# RF19_Sensor_CAN_Module_MCU.net
KiCad netlist of a schematic drawn in Altium Designer
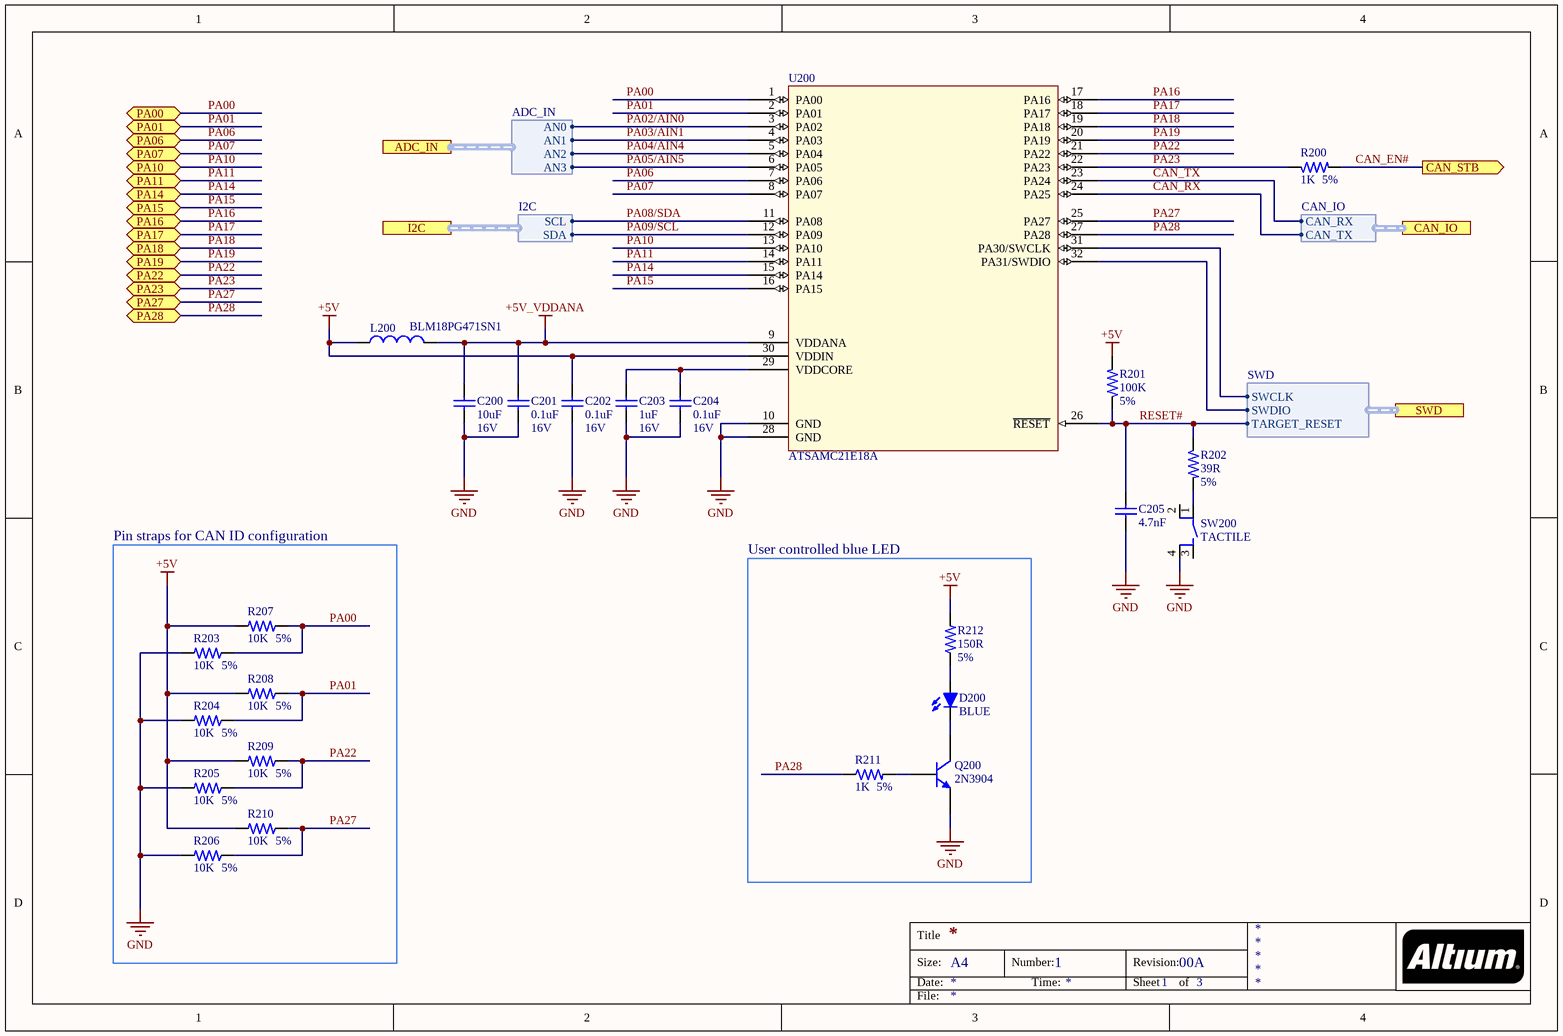
[diagram p0: RF19_Sensor_CAN_Module_MCU.SchDoc]

(export (version "E")
  (design (tool "Eeschema 10.0.6"))
  (components
    (comp (ref "C200")
      (value "10uF")
      (footprint "C0603")
      (description "Ceramic cap, 10uF +/-10% 16V X5R 0603")
      (fields (field (name "VOLTAGE") "16V") (field (name "Comment") "CERAMIC CAP"))
      (libsource (lib "Custom") (part "C010U10P16VX5R0603"))
    )
    (comp (ref "C201")
      (value "0.1uF")
      (footprint "C0402")
      (description "Ceramic cap, 0.1uF +/-10% 16V X5R 0402")
      (fields (field (name "VOLTAGE") "16V") (field (name "Comment") "CERAMIC CAP"))
      (libsource (lib "Custom") (part "C00U110P16VX5R0402"))
    )
    (comp (ref "C202")
      (value "0.1uF")
      (footprint "C0402")
      (description "Ceramic cap, 0.1uF +/-10% 16V X5R 0402")
      (fields (field (name "VOLTAGE") "16V") (field (name "Comment") "CERAMIC CAP"))
      (libsource (lib "Custom") (part "C00U110P16VX5R0402"))
    )
    (comp (ref "C203")
      (value "1uF")
      (footprint "C0402")
      (description "Ceramic cap, 1uF +/-10% 16V X5R 0402")
      (fields (field (name "VOLTAGE") "16V") (field (name "Comment") "CERAMIC CAP"))
      (libsource (lib "Custom") (part "C001U10P16VX5R0402"))
    )
    (comp (ref "C204")
      (value "0.1uF")
      (footprint "C0402")
      (description "Ceramic cap, 0.1uF +/-10% 16V X5R 0402")
      (fields (field (name "VOLTAGE") "16V") (field (name "Comment") "CERAMIC CAP"))
      (libsource (lib "Custom") (part "C00U110P16VX5R0402"))
    )
    (comp (ref "C205")
      (value "4.7nF")
      (footprint "C0402")
      (description "Ceramic capacitor")
      (fields (field (name "Comment") "CAP CERAMIC"))
      (libsource (lib "Custom") (part "CAP CERAMIC"))
    )
    (comp (ref "D200")
      (value "BLUE")
      (footprint "0603 LED")
      (description "LED Blue, 0603 3.3V 20mA")
      (libsource (lib "Custom") (part "D0603BLUE"))
    )
    (comp (ref "L200")
      (value "BLM18PG471SN1")
      (footprint "L0603_MURATA")
      (description "SMD RF inductor 0603. Z=470Ohm (@100MHz), Max R(dc)=0.65Ohm, Max current=1A")
      (fields (field (name "TOLERANCE") "±25%") (field (name "MANUFACTURER") "Murata"))
      (libsource (lib "AltiumDbLib") (part "INDUCTOR"))
    )
    (comp (ref "Q200")
      (value "2N3904")
      (footprint "SOT323-3L")
      (description "NPN Bipolar Transistor")
      (fields (field (name "PUBLISHER") "Altium Limited"))
      (libsource (lib "Miscellaneous Devices") (part "QNPN"))
    )
    (comp (ref "R200")
      (value "1K")
      (footprint "R0402")
      (description "Resistor 1K 5% 0402 1/16W")
      (fields (field (name "TOLERANCE") "5%") (field (name "Comment") "R001K50P0402063"))
      (libsource (lib "Custom") (part "R001K50P0402063"))
    )
    (comp (ref "R201")
      (value "100K")
      (footprint "R0402")
      (description "Resistor 100K 5% 0402 1/16W")
      (fields (field (name "TOLERANCE") "5%") (field (name "Comment") "R100K50P0402063"))
      (libsource (lib "Custom") (part "R100K50P0402063"))
    )
    (comp (ref "R202")
      (value "39R")
      (footprint "R0402")
      (description "Resistor 39R 5% 0402 1/16W")
      (fields (field (name "TOLERANCE") "5%") (field (name "Comment") "R039R50P0402063"))
      (libsource (lib "Custom") (part "R039R50P0402063"))
    )
    (comp (ref "R203")
      (value "10K")
      (footprint "R0402")
      (description "Resistor 10K 5% 0402 1/16W")
      (fields (field (name "TOLERANCE") "5%") (field (name "Comment") "R010K50P0402063"))
      (libsource (lib "Custom") (part "R010K50P0402063"))
    )
    (comp (ref "R204")
      (value "10K")
      (footprint "R0402")
      (description "Resistor 10K 5% 0402 1/16W")
      (fields (field (name "TOLERANCE") "5%") (field (name "Comment") "R010K50P0402063"))
      (libsource (lib "Custom") (part "R010K50P0402063"))
    )
    (comp (ref "R205")
      (value "10K")
      (footprint "R0402")
      (description "Resistor 10K 5% 0402 1/16W")
      (fields (field (name "TOLERANCE") "5%") (field (name "Comment") "R010K50P0402063"))
      (libsource (lib "Custom") (part "R010K50P0402063"))
    )
    (comp (ref "R206")
      (value "10K")
      (footprint "R0402")
      (description "Resistor 10K 5% 0402 1/16W")
      (fields (field (name "TOLERANCE") "5%") (field (name "Comment") "R010K50P0402063"))
      (libsource (lib "Custom") (part "R010K50P0402063"))
    )
    (comp (ref "R207")
      (value "10K")
      (footprint "R0402")
      (description "Resistor 10K 5% 0402 1/16W")
      (fields (field (name "TOLERANCE") "5%") (field (name "Comment") "R010K50P0402063"))
      (libsource (lib "Custom") (part "R010K50P0402063"))
    )
    (comp (ref "R208")
      (value "10K")
      (footprint "R0402")
      (description "Resistor 10K 5% 0402 1/16W")
      (fields (field (name "TOLERANCE") "5%") (field (name "Comment") "R010K50P0402063"))
      (libsource (lib "Custom") (part "R010K50P0402063"))
    )
    (comp (ref "R209")
      (value "10K")
      (footprint "R0402")
      (description "Resistor 10K 5% 0402 1/16W")
      (fields (field (name "TOLERANCE") "5%") (field (name "Comment") "R010K50P0402063"))
      (libsource (lib "Custom") (part "R010K50P0402063"))
    )
    (comp (ref "R210")
      (value "10K")
      (footprint "R0402")
      (description "Resistor 10K 5% 0402 1/16W")
      (fields (field (name "TOLERANCE") "5%") (field (name "Comment") "R010K50P0402063"))
      (libsource (lib "Custom") (part "R010K50P0402063"))
    )
    (comp (ref "R211")
      (value "1K")
      (footprint "R0402")
      (description "Resistor 1K 5% 0402 1/16W")
      (fields (field (name "TOLERANCE") "5%") (field (name "Comment") "R001K50P0402063"))
      (libsource (lib "Custom") (part "R001K50P0402063"))
    )
    (comp (ref "R212")
      (value "150R")
      (footprint "R0402")
      (description "Resistor 150R 5% 0402 1/16W")
      (fields (field (name "TOLERANCE") "5%") (field (name "Comment") "R150R50P0402063"))
      (libsource (lib "Custom") (part "R150R50P0402063"))
    )
    (comp (ref "SW200")
      (value "TACTILE")
      (footprint "TACTILE GULL WING KMR7")
      (description "Tactile Switch SPST-NO Top Actuated Surface Mount")
      (libsource (lib "Custom") (part "SWITCH TACTILE ALT"))
    )
    (comp (ref "U200")
      (value "ATSAMC21E18A")
      (footprint "ATMEL_TQFP-32")
      (description "Atmel SAM ARM Cortex-M0+ 32-bit MCU")
      (libsource (lib "Custom") (part "ATSAMC21E18A"))
    )
  )
  (nets
    (net (code "5") (name "+5V") (class "Default")
      (node (ref "C202") (pin "1") (pinfunction "1_1") (pintype "passive"))
      (node (ref "L200") (pin "1") (pinfunction "1_1") (pintype "passive"))
      (node (ref "R201") (pin "2") (pinfunction "2_2") (pintype "passive"))
      (node (ref "R207") (pin "2") (pinfunction "2_2") (pintype "passive"))
      (node (ref "R208") (pin "2") (pinfunction "2_2") (pintype "passive"))
      (node (ref "R209") (pin "2") (pinfunction "2_2") (pintype "passive"))
      (node (ref "R210") (pin "2") (pinfunction "2_2") (pintype "passive"))
      (node (ref "R212") (pin "2") (pinfunction "2_2") (pintype "passive"))
      (node (ref "U200") (pin "30") (pinfunction "VDDIN_30") (pintype "power_in"))
    )
    (net (code "6") (name "+5V_VDDANA") (class "Default")
      (node (ref "C200") (pin "1") (pinfunction "1_1") (pintype "passive"))
      (node (ref "C201") (pin "1") (pinfunction "1_1") (pintype "passive"))
      (node (ref "L200") (pin "2") (pinfunction "2_2") (pintype "passive"))
      (node (ref "U200") (pin "9") (pinfunction "VDDANA_9") (pintype "power_in"))
    )
    (net (code "7") (name "/CAN_EN#") (class "Default")
      (node (ref "R200") (pin "2") (pinfunction "2_2") (pintype "passive"))
    )
    (net (code "8") (name "/CAN_RX") (class "Default")
      (node (ref "U200") (pin "24") (pinfunction "PA25_24") (pintype "bidirectional"))
    )
    (net (code "9") (name "/CAN_TX") (class "Default")
      (node (ref "U200") (pin "23") (pinfunction "PA24_23") (pintype "bidirectional"))
    )
    (net (code "10") (name "/PA00") (class "Default")
      (node (ref "R203") (pin "1") (pinfunction "1_1") (pintype "passive"))
      (node (ref "R207") (pin "1") (pinfunction "1_1") (pintype "passive"))
      (node (ref "U200") (pin "1") (pinfunction "PA00_1") (pintype "bidirectional"))
    )
    (net (code "11") (name "/PA01") (class "Default")
      (node (ref "R204") (pin "1") (pinfunction "1_1") (pintype "passive"))
      (node (ref "R208") (pin "1") (pinfunction "1_1") (pintype "passive"))
      (node (ref "U200") (pin "2") (pinfunction "PA01_2") (pintype "bidirectional"))
    )
    (net (code "12") (name "/PA02{slash}AIN0") (class "Default")
      (node (ref "U200") (pin "3") (pinfunction "PA02_3") (pintype "bidirectional"))
    )
    (net (code "13") (name "/PA03{slash}AIN1") (class "Default")
      (node (ref "U200") (pin "4") (pinfunction "PA03_4") (pintype "bidirectional"))
    )
    (net (code "14") (name "/PA04{slash}AIN4") (class "Default")
      (node (ref "U200") (pin "5") (pinfunction "PA04_5") (pintype "bidirectional"))
    )
    (net (code "15") (name "/PA05{slash}AIN5") (class "Default")
      (node (ref "U200") (pin "6") (pinfunction "PA05_6") (pintype "bidirectional"))
    )
    (net (code "16") (name "/PA06") (class "Default")
      (node (ref "U200") (pin "7") (pinfunction "PA06_7") (pintype "bidirectional"))
    )
    (net (code "17") (name "/PA07") (class "Default")
      (node (ref "U200") (pin "8") (pinfunction "PA07_8") (pintype "bidirectional"))
    )
    (net (code "18") (name "/PA08{slash}SDA") (class "Default")
      (node (ref "U200") (pin "11") (pinfunction "PA08_11") (pintype "bidirectional"))
    )
    (net (code "19") (name "/PA09{slash}SCL") (class "Default")
      (node (ref "U200") (pin "12") (pinfunction "PA09_12") (pintype "bidirectional"))
    )
    (net (code "20") (name "/PA10") (class "Default")
      (node (ref "U200") (pin "13") (pinfunction "PA10_13") (pintype "bidirectional"))
    )
    (net (code "21") (name "/PA11") (class "Default")
      (node (ref "U200") (pin "14") (pinfunction "PA11_14") (pintype "bidirectional"))
    )
    (net (code "22") (name "/PA14") (class "Default")
      (node (ref "U200") (pin "15") (pinfunction "PA14_15") (pintype "bidirectional"))
    )
    (net (code "23") (name "/PA15") (class "Default")
      (node (ref "U200") (pin "16") (pinfunction "PA15_16") (pintype "bidirectional"))
    )
    (net (code "24") (name "/PA16") (class "Default")
      (node (ref "U200") (pin "17") (pinfunction "PA16_17") (pintype "bidirectional"))
    )
    (net (code "25") (name "/PA17") (class "Default")
      (node (ref "U200") (pin "18") (pinfunction "PA17_18") (pintype "bidirectional"))
    )
    (net (code "26") (name "/PA18") (class "Default")
      (node (ref "U200") (pin "19") (pinfunction "PA18_19") (pintype "bidirectional"))
    )
    (net (code "27") (name "/PA19") (class "Default")
      (node (ref "U200") (pin "20") (pinfunction "PA19_20") (pintype "bidirectional"))
    )
    (net (code "28") (name "/PA22") (class "Default")
      (node (ref "R205") (pin "1") (pinfunction "1_1") (pintype "passive"))
      (node (ref "R209") (pin "1") (pinfunction "1_1") (pintype "passive"))
      (node (ref "U200") (pin "21") (pinfunction "PA22_21") (pintype "bidirectional"))
    )
    (net (code "29") (name "/PA23") (class "Default")
      (node (ref "R200") (pin "1") (pinfunction "1_1") (pintype "passive"))
      (node (ref "U200") (pin "22") (pinfunction "PA23_22") (pintype "bidirectional"))
    )
    (net (code "30") (name "/PA27") (class "Default")
      (node (ref "R206") (pin "1") (pinfunction "1_1") (pintype "passive"))
      (node (ref "R210") (pin "1") (pinfunction "1_1") (pintype "passive"))
      (node (ref "U200") (pin "25") (pinfunction "PA27_25") (pintype "bidirectional"))
    )
    (net (code "31") (name "/PA28") (class "Default")
      (node (ref "R211") (pin "1") (pinfunction "1_1") (pintype "passive"))
      (node (ref "U200") (pin "27") (pinfunction "PA28_27") (pintype "bidirectional"))
    )
    (net (code "32") (name "/RESET#") (class "Default")
      (node (ref "C205") (pin "1") (pinfunction "1_1") (pintype "passive"))
      (node (ref "R201") (pin "1") (pinfunction "1_1") (pintype "passive"))
      (node (ref "R202") (pin "1") (pinfunction "1_1") (pintype "passive"))
      (node (ref "U200") (pin "26") (pinfunction "~{RESET}_26") (pintype "input"))
    )
    (net (code "33") (name "/SWCLK") (class "Default")
      (node (ref "U200") (pin "31") (pinfunction "PA30/SWCLK_31") (pintype "bidirectional"))
    )
    (net (code "34") (name "/SWDIO") (class "Default")
      (node (ref "U200") (pin "32") (pinfunction "PA31/SWDIO_32") (pintype "bidirectional"))
    )
    (net (code "39") (name "GND") (class "Default")
      (node (ref "C200") (pin "2") (pinfunction "2_2") (pintype "passive"))
      (node (ref "C201") (pin "2") (pinfunction "2_2") (pintype "passive"))
      (node (ref "C202") (pin "2") (pinfunction "2_2") (pintype "passive"))
      (node (ref "C203") (pin "2") (pinfunction "2_2") (pintype "passive"))
      (node (ref "C204") (pin "2") (pinfunction "2_2") (pintype "passive"))
      (node (ref "C205") (pin "2") (pinfunction "2_2") (pintype "passive"))
      (node (ref "Q200") (pin "3") (pinfunction "E_3") (pintype "passive"))
      (node (ref "R203") (pin "2") (pinfunction "2_2") (pintype "passive"))
      (node (ref "R204") (pin "2") (pinfunction "2_2") (pintype "passive"))
      (node (ref "R205") (pin "2") (pinfunction "2_2") (pintype "passive"))
      (node (ref "R206") (pin "2") (pinfunction "2_2") (pintype "passive"))
      (node (ref "SW200") (pin "4") (pinfunction "4_4") (pintype "passive"))
      (node (ref "U200") (pin "10") (pinfunction "GND_10") (pintype "power_in"))
      (node (ref "U200") (pin "28") (pinfunction "GND_28") (pintype "power_in"))
    )
    (net (code "40") (name "Net-(D200-PadA)") (class "Default")
      (node (ref "D200") (pin "A") (pinfunction "A_A") (pintype "passive"))
      (node (ref "R212") (pin "1") (pinfunction "1_1") (pintype "passive"))
    )
    (net (code "41") (name "Net-(Q200-B)") (class "Default")
      (node (ref "Q200") (pin "2") (pinfunction "B_2") (pintype "passive"))
      (node (ref "R211") (pin "2") (pinfunction "2_2") (pintype "passive"))
    )
    (net (code "42") (name "Net-(Q200-C)") (class "Default")
      (node (ref "D200") (pin "C") (pinfunction "C_C") (pintype "passive"))
      (node (ref "Q200") (pin "1") (pinfunction "C_1") (pintype "passive"))
    )
    (net (code "43") (name "Net-(R202-Pad2)") (class "Default")
      (node (ref "R202") (pin "2") (pinfunction "2_2") (pintype "passive"))
      (node (ref "SW200") (pin "1") (pinfunction "1_1") (pintype "passive"))
    )
    (net (code "44") (name "Net-(U200-VDDCORE)") (class "Default")
      (node (ref "C203") (pin "1") (pinfunction "1_1") (pintype "passive"))
      (node (ref "C204") (pin "1") (pinfunction "1_1") (pintype "passive"))
      (node (ref "U200") (pin "29") (pinfunction "VDDCORE_29") (pintype "power_in"))
    )
    (net (code "45") (name "unconnected-(SW200-Pad2)") (class "Default")
      (node (ref "SW200") (pin "2") (pinfunction "2_2") (pintype "passive"))
    )
    (net (code "46") (name "unconnected-(SW200-Pad3)") (class "Default")
      (node (ref "SW200") (pin "3") (pinfunction "3_3") (pintype "passive"))
    )
  )
)
